# FIT_FPGA_A-B-C.net
KiCad netlist of a schematic drawn in Altium Designer
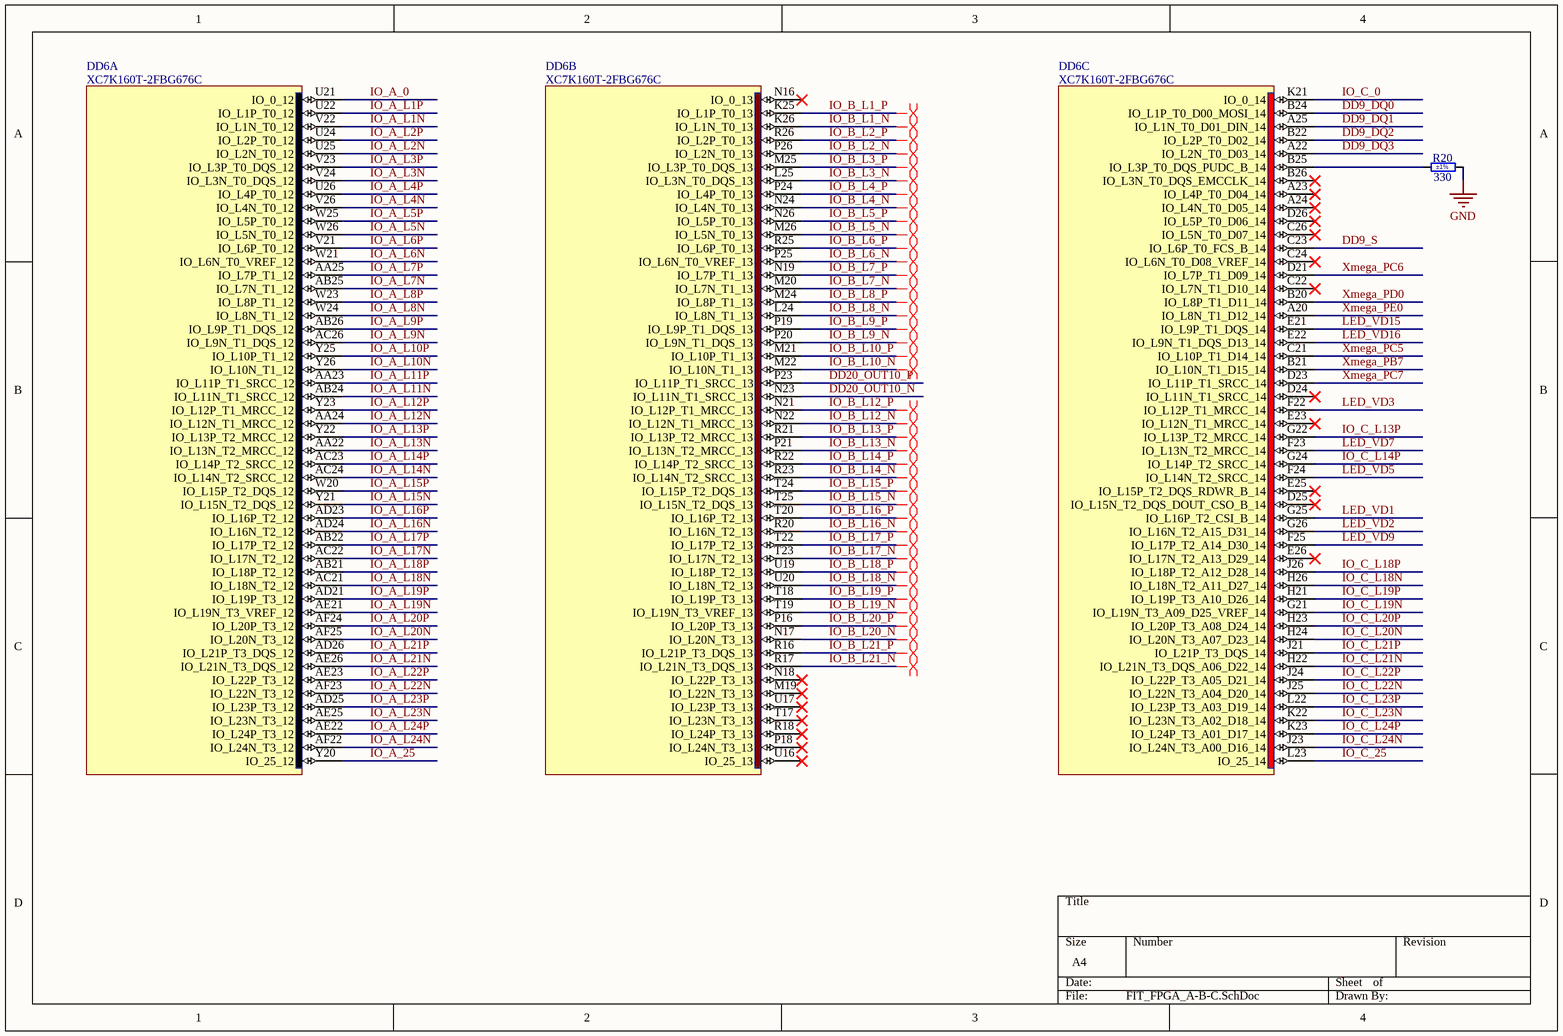
[diagram p0: FIT_FPGA_A-B-C.SchDoc]

(export (version "E")
  (design (tool "Eeschema 10.0.6"))
  (components
    (comp (ref "DD6")
      (value "XC7K160T-2FBG676C")
      (footprint "BGA676C100P26X26_2700X2700X254")
      (description "KINTEX-7, FPGA, 676-Ball BGA, Pb-Free")
      (fields (field (name "MANUFACTURER") "XILINX") (field (name "AUTHOR") "CERN DEM BC"))
      (libsource (lib "ICs And Semiconductors") (part "XC7K160T-xFBG676"))
    )
    (comp (ref "R20")
      (value "330")
      (footprint "RESC2012X60N")
      (description "Resistor - 1%")
      (fields
        (field (name "TOLERANCE") "±1%")
        (field (name "PART NUMBER") "R0805_330R_1%_0.125W_100PPM")
        (field (name "POWER") "0.125W")
        (field (name "AUTHOR") "CERN DEM JLC")
      )
      (libsource (lib "Resistors") (part "Resistor - 1%"))
    )
  )
  (nets
    (net (code "1") (name "/DD9_DQ0") (class "Default")
      (node (ref "DD6") (pin "B24") (pinfunction "IO_L1P_T0_D00_MOSI_14_B24") (pintype "bidirectional"))
    )
    (net (code "2") (name "/DD9_DQ1") (class "Default")
      (node (ref "DD6") (pin "A25") (pinfunction "IO_L1N_T0_D01_DIN_14_A25") (pintype "bidirectional"))
    )
    (net (code "3") (name "/DD9_DQ2") (class "Default")
      (node (ref "DD6") (pin "B22") (pinfunction "IO_L2P_T0_D02_14_B22") (pintype "bidirectional"))
    )
    (net (code "4") (name "/DD9_DQ3") (class "Default")
      (node (ref "DD6") (pin "A22") (pinfunction "IO_L2N_T0_D03_14_A22") (pintype "bidirectional"))
    )
    (net (code "5") (name "/DD9_S") (class "Default")
      (node (ref "DD6") (pin "C23") (pinfunction "IO_L6P_T0_FCS_B_14_C23") (pintype "bidirectional"))
    )
    (net (code "6") (name "/DD20_OUT10_N") (class "Default")
      (node (ref "DD6") (pin "N23") (pinfunction "IO_L11N_T1_SRCC_13_N23") (pintype "bidirectional"))
    )
    (net (code "7") (name "/DD20_OUT10_P") (class "Default")
      (node (ref "DD6") (pin "P23") (pinfunction "IO_L11P_T1_SRCC_13_P23") (pintype "bidirectional"))
    )
    (net (code "8") (name "/IO_A_0") (class "Default")
      (node (ref "DD6") (pin "U21") (pinfunction "IO_0_12_U21") (pintype "bidirectional"))
    )
    (net (code "9") (name "/IO_A_25") (class "Default")
      (node (ref "DD6") (pin "Y20") (pinfunction "IO_25_12_Y20") (pintype "bidirectional"))
    )
    (net (code "10") (name "/IO_A_L1N") (class "Default")
      (node (ref "DD6") (pin "V22") (pinfunction "IO_L1N_T0_12_V22") (pintype "bidirectional"))
    )
    (net (code "11") (name "/IO_A_L1P") (class "Default")
      (node (ref "DD6") (pin "U22") (pinfunction "IO_L1P_T0_12_U22") (pintype "bidirectional"))
    )
    (net (code "12") (name "/IO_A_L2N") (class "Default")
      (node (ref "DD6") (pin "U25") (pinfunction "IO_L2N_T0_12_U25") (pintype "bidirectional"))
    )
    (net (code "13") (name "/IO_A_L2P") (class "Default")
      (node (ref "DD6") (pin "U24") (pinfunction "IO_L2P_T0_12_U24") (pintype "bidirectional"))
    )
    (net (code "14") (name "/IO_A_L3N") (class "Default")
      (node (ref "DD6") (pin "V24") (pinfunction "IO_L3N_T0_DQS_12_V24") (pintype "bidirectional"))
    )
    (net (code "15") (name "/IO_A_L3P") (class "Default")
      (node (ref "DD6") (pin "V23") (pinfunction "IO_L3P_T0_DQS_12_V23") (pintype "bidirectional"))
    )
    (net (code "16") (name "/IO_A_L4N") (class "Default")
      (node (ref "DD6") (pin "V26") (pinfunction "IO_L4N_T0_12_V26") (pintype "bidirectional"))
    )
    (net (code "17") (name "/IO_A_L4P") (class "Default")
      (node (ref "DD6") (pin "U26") (pinfunction "IO_L4P_T0_12_U26") (pintype "bidirectional"))
    )
    (net (code "18") (name "/IO_A_L5N") (class "Default")
      (node (ref "DD6") (pin "W26") (pinfunction "IO_L5N_T0_12_W26") (pintype "bidirectional"))
    )
    (net (code "19") (name "/IO_A_L5P") (class "Default")
      (node (ref "DD6") (pin "W25") (pinfunction "IO_L5P_T0_12_W25") (pintype "bidirectional"))
    )
    (net (code "20") (name "/IO_A_L6N") (class "Default")
      (node (ref "DD6") (pin "W21") (pinfunction "IO_L6N_T0_VREF_12_W21") (pintype "bidirectional"))
    )
    (net (code "21") (name "/IO_A_L6P") (class "Default")
      (node (ref "DD6") (pin "V21") (pinfunction "IO_L6P_T0_12_V21") (pintype "bidirectional"))
    )
    (net (code "22") (name "/IO_A_L7N") (class "Default")
      (node (ref "DD6") (pin "AB25") (pinfunction "IO_L7N_T1_12_AB25") (pintype "bidirectional"))
    )
    (net (code "23") (name "/IO_A_L7P") (class "Default")
      (node (ref "DD6") (pin "AA25") (pinfunction "IO_L7P_T1_12_AA25") (pintype "bidirectional"))
    )
    (net (code "24") (name "/IO_A_L8N") (class "Default")
      (node (ref "DD6") (pin "W24") (pinfunction "IO_L8N_T1_12_W24") (pintype "bidirectional"))
    )
    (net (code "25") (name "/IO_A_L8P") (class "Default")
      (node (ref "DD6") (pin "W23") (pinfunction "IO_L8P_T1_12_W23") (pintype "bidirectional"))
    )
    (net (code "26") (name "/IO_A_L9N") (class "Default")
      (node (ref "DD6") (pin "AC26") (pinfunction "IO_L9N_T1_DQS_12_AC26") (pintype "bidirectional"))
    )
    (net (code "27") (name "/IO_A_L9P") (class "Default")
      (node (ref "DD6") (pin "AB26") (pinfunction "IO_L9P_T1_DQS_12_AB26") (pintype "bidirectional"))
    )
    (net (code "28") (name "/IO_A_L10N") (class "Default")
      (node (ref "DD6") (pin "Y26") (pinfunction "IO_L10N_T1_12_Y26") (pintype "bidirectional"))
    )
    (net (code "29") (name "/IO_A_L10P") (class "Default")
      (node (ref "DD6") (pin "Y25") (pinfunction "IO_L10P_T1_12_Y25") (pintype "bidirectional"))
    )
    (net (code "30") (name "/IO_A_L11N") (class "Default")
      (node (ref "DD6") (pin "AB24") (pinfunction "IO_L11N_T1_SRCC_12_AB24") (pintype "bidirectional"))
    )
    (net (code "31") (name "/IO_A_L11P") (class "Default")
      (node (ref "DD6") (pin "AA23") (pinfunction "IO_L11P_T1_SRCC_12_AA23") (pintype "bidirectional"))
    )
    (net (code "32") (name "/IO_A_L12N") (class "Default")
      (node (ref "DD6") (pin "AA24") (pinfunction "IO_L12N_T1_MRCC_12_AA24") (pintype "bidirectional"))
    )
    (net (code "33") (name "/IO_A_L12P") (class "Default")
      (node (ref "DD6") (pin "Y23") (pinfunction "IO_L12P_T1_MRCC_12_Y23") (pintype "bidirectional"))
    )
    (net (code "34") (name "/IO_A_L13N") (class "Default")
      (node (ref "DD6") (pin "AA22") (pinfunction "IO_L13N_T2_MRCC_12_AA22") (pintype "bidirectional"))
    )
    (net (code "35") (name "/IO_A_L13P") (class "Default")
      (node (ref "DD6") (pin "Y22") (pinfunction "IO_L13P_T2_MRCC_12_Y22") (pintype "bidirectional"))
    )
    (net (code "36") (name "/IO_A_L14N") (class "Default")
      (node (ref "DD6") (pin "AC24") (pinfunction "IO_L14N_T2_SRCC_12_AC24") (pintype "bidirectional"))
    )
    (net (code "37") (name "/IO_A_L14P") (class "Default")
      (node (ref "DD6") (pin "AC23") (pinfunction "IO_L14P_T2_SRCC_12_AC23") (pintype "bidirectional"))
    )
    (net (code "38") (name "/IO_A_L15N") (class "Default")
      (node (ref "DD6") (pin "Y21") (pinfunction "IO_L15N_T2_DQS_12_Y21") (pintype "bidirectional"))
    )
    (net (code "39") (name "/IO_A_L15P") (class "Default")
      (node (ref "DD6") (pin "W20") (pinfunction "IO_L15P_T2_DQS_12_W20") (pintype "bidirectional"))
    )
    (net (code "40") (name "/IO_A_L16N") (class "Default")
      (node (ref "DD6") (pin "AD24") (pinfunction "IO_L16N_T2_12_AD24") (pintype "bidirectional"))
    )
    (net (code "41") (name "/IO_A_L16P") (class "Default")
      (node (ref "DD6") (pin "AD23") (pinfunction "IO_L16P_T2_12_AD23") (pintype "bidirectional"))
    )
    (net (code "42") (name "/IO_A_L17N") (class "Default")
      (node (ref "DD6") (pin "AC22") (pinfunction "IO_L17N_T2_12_AC22") (pintype "bidirectional"))
    )
    (net (code "43") (name "/IO_A_L17P") (class "Default")
      (node (ref "DD6") (pin "AB22") (pinfunction "IO_L17P_T2_12_AB22") (pintype "bidirectional"))
    )
    (net (code "44") (name "/IO_A_L18N") (class "Default")
      (node (ref "DD6") (pin "AC21") (pinfunction "IO_L18N_T2_12_AC21") (pintype "bidirectional"))
    )
    (net (code "45") (name "/IO_A_L18P") (class "Default")
      (node (ref "DD6") (pin "AB21") (pinfunction "IO_L18P_T2_12_AB21") (pintype "bidirectional"))
    )
    (net (code "46") (name "/IO_A_L19N") (class "Default")
      (node (ref "DD6") (pin "AE21") (pinfunction "IO_L19N_T3_VREF_12_AE21") (pintype "bidirectional"))
    )
    (net (code "47") (name "/IO_A_L19P") (class "Default")
      (node (ref "DD6") (pin "AD21") (pinfunction "IO_L19P_T3_12_AD21") (pintype "bidirectional"))
    )
    (net (code "48") (name "/IO_A_L20N") (class "Default")
      (node (ref "DD6") (pin "AF25") (pinfunction "IO_L20N_T3_12_AF25") (pintype "bidirectional"))
    )
    (net (code "49") (name "/IO_A_L20P") (class "Default")
      (node (ref "DD6") (pin "AF24") (pinfunction "IO_L20P_T3_12_AF24") (pintype "bidirectional"))
    )
    (net (code "50") (name "/IO_A_L21N") (class "Default")
      (node (ref "DD6") (pin "AE26") (pinfunction "IO_L21N_T3_DQS_12_AE26") (pintype "bidirectional"))
    )
    (net (code "51") (name "/IO_A_L21P") (class "Default")
      (node (ref "DD6") (pin "AD26") (pinfunction "IO_L21P_T3_DQS_12_AD26") (pintype "bidirectional"))
    )
    (net (code "52") (name "/IO_A_L22N") (class "Default")
      (node (ref "DD6") (pin "AF23") (pinfunction "IO_L22N_T3_12_AF23") (pintype "bidirectional"))
    )
    (net (code "53") (name "/IO_A_L22P") (class "Default")
      (node (ref "DD6") (pin "AE23") (pinfunction "IO_L22P_T3_12_AE23") (pintype "bidirectional"))
    )
    (net (code "54") (name "/IO_A_L23N") (class "Default")
      (node (ref "DD6") (pin "AE25") (pinfunction "IO_L23N_T3_12_AE25") (pintype "bidirectional"))
    )
    (net (code "55") (name "/IO_A_L23P") (class "Default")
      (node (ref "DD6") (pin "AD25") (pinfunction "IO_L23P_T3_12_AD25") (pintype "bidirectional"))
    )
    (net (code "56") (name "/IO_A_L24N") (class "Default")
      (node (ref "DD6") (pin "AF22") (pinfunction "IO_L24N_T3_12_AF22") (pintype "bidirectional"))
    )
    (net (code "57") (name "/IO_A_L24P") (class "Default")
      (node (ref "DD6") (pin "AE22") (pinfunction "IO_L24P_T3_12_AE22") (pintype "bidirectional"))
    )
    (net (code "58") (name "/IO_B_L1_N") (class "Default")
      (node (ref "DD6") (pin "K26") (pinfunction "IO_L1N_T0_13_K26") (pintype "bidirectional"))
    )
    (net (code "59") (name "/IO_B_L1_P") (class "Default")
      (node (ref "DD6") (pin "K25") (pinfunction "IO_L1P_T0_13_K25") (pintype "bidirectional"))
    )
    (net (code "60") (name "/IO_B_L2_N") (class "Default")
      (node (ref "DD6") (pin "P26") (pinfunction "IO_L2N_T0_13_P26") (pintype "bidirectional"))
    )
    (net (code "61") (name "/IO_B_L2_P") (class "Default")
      (node (ref "DD6") (pin "R26") (pinfunction "IO_L2P_T0_13_R26") (pintype "bidirectional"))
    )
    (net (code "62") (name "/IO_B_L3_N") (class "Default")
      (node (ref "DD6") (pin "L25") (pinfunction "IO_L3N_T0_DQS_13_L25") (pintype "bidirectional"))
    )
    (net (code "63") (name "/IO_B_L3_P") (class "Default")
      (node (ref "DD6") (pin "M25") (pinfunction "IO_L3P_T0_DQS_13_M25") (pintype "bidirectional"))
    )
    (net (code "64") (name "/IO_B_L4_N") (class "Default")
      (node (ref "DD6") (pin "N24") (pinfunction "IO_L4N_T0_13_N24") (pintype "bidirectional"))
    )
    (net (code "65") (name "/IO_B_L4_P") (class "Default")
      (node (ref "DD6") (pin "P24") (pinfunction "IO_L4P_T0_13_P24") (pintype "bidirectional"))
    )
    (net (code "66") (name "/IO_B_L5_N") (class "Default")
      (node (ref "DD6") (pin "M26") (pinfunction "IO_L5N_T0_13_M26") (pintype "bidirectional"))
    )
    (net (code "67") (name "/IO_B_L5_P") (class "Default")
      (node (ref "DD6") (pin "N26") (pinfunction "IO_L5P_T0_13_N26") (pintype "bidirectional"))
    )
    (net (code "68") (name "/IO_B_L6_N") (class "Default")
      (node (ref "DD6") (pin "P25") (pinfunction "IO_L6N_T0_VREF_13_P25") (pintype "bidirectional"))
    )
    (net (code "69") (name "/IO_B_L6_P") (class "Default")
      (node (ref "DD6") (pin "R25") (pinfunction "IO_L6P_T0_13_R25") (pintype "bidirectional"))
    )
    (net (code "70") (name "/IO_B_L7_N") (class "Default")
      (node (ref "DD6") (pin "M20") (pinfunction "IO_L7N_T1_13_M20") (pintype "bidirectional"))
    )
    (net (code "71") (name "/IO_B_L7_P") (class "Default")
      (node (ref "DD6") (pin "N19") (pinfunction "IO_L7P_T1_13_N19") (pintype "bidirectional"))
    )
    (net (code "72") (name "/IO_B_L8_N") (class "Default")
      (node (ref "DD6") (pin "L24") (pinfunction "IO_L8N_T1_13_L24") (pintype "bidirectional"))
    )
    (net (code "73") (name "/IO_B_L8_P") (class "Default")
      (node (ref "DD6") (pin "M24") (pinfunction "IO_L8P_T1_13_M24") (pintype "bidirectional"))
    )
    (net (code "74") (name "/IO_B_L9_N") (class "Default")
      (node (ref "DD6") (pin "P20") (pinfunction "IO_L9N_T1_DQS_13_P20") (pintype "bidirectional"))
    )
    (net (code "75") (name "/IO_B_L9_P") (class "Default")
      (node (ref "DD6") (pin "P19") (pinfunction "IO_L9P_T1_DQS_13_P19") (pintype "bidirectional"))
    )
    (net (code "76") (name "/IO_B_L10_N") (class "Default")
      (node (ref "DD6") (pin "M22") (pinfunction "IO_L10N_T1_13_M22") (pintype "bidirectional"))
    )
    (net (code "77") (name "/IO_B_L10_P") (class "Default")
      (node (ref "DD6") (pin "M21") (pinfunction "IO_L10P_T1_13_M21") (pintype "bidirectional"))
    )
    (net (code "78") (name "/IO_B_L12_N") (class "Default")
      (node (ref "DD6") (pin "N22") (pinfunction "IO_L12N_T1_MRCC_13_N22") (pintype "bidirectional"))
    )
    (net (code "79") (name "/IO_B_L12_P") (class "Default")
      (node (ref "DD6") (pin "N21") (pinfunction "IO_L12P_T1_MRCC_13_N21") (pintype "bidirectional"))
    )
    (net (code "80") (name "/IO_B_L13_N") (class "Default")
      (node (ref "DD6") (pin "P21") (pinfunction "IO_L13N_T2_MRCC_13_P21") (pintype "bidirectional"))
    )
    (net (code "81") (name "/IO_B_L13_P") (class "Default")
      (node (ref "DD6") (pin "R21") (pinfunction "IO_L13P_T2_MRCC_13_R21") (pintype "bidirectional"))
    )
    (net (code "82") (name "/IO_B_L14_N") (class "Default")
      (node (ref "DD6") (pin "R23") (pinfunction "IO_L14N_T2_SRCC_13_R23") (pintype "bidirectional"))
    )
    (net (code "83") (name "/IO_B_L14_P") (class "Default")
      (node (ref "DD6") (pin "R22") (pinfunction "IO_L14P_T2_SRCC_13_R22") (pintype "bidirectional"))
    )
    (net (code "84") (name "/IO_B_L15_N") (class "Default")
      (node (ref "DD6") (pin "T25") (pinfunction "IO_L15N_T2_DQS_13_T25") (pintype "bidirectional"))
    )
    (net (code "85") (name "/IO_B_L15_P") (class "Default")
      (node (ref "DD6") (pin "T24") (pinfunction "IO_L15P_T2_DQS_13_T24") (pintype "bidirectional"))
    )
    (net (code "86") (name "/IO_B_L16_N") (class "Default")
      (node (ref "DD6") (pin "R20") (pinfunction "IO_L16N_T2_13_R20") (pintype "bidirectional"))
    )
    (net (code "87") (name "/IO_B_L16_P") (class "Default")
      (node (ref "DD6") (pin "T20") (pinfunction "IO_L16P_T2_13_T20") (pintype "bidirectional"))
    )
    (net (code "88") (name "/IO_B_L17_N") (class "Default")
      (node (ref "DD6") (pin "T23") (pinfunction "IO_L17N_T2_13_T23") (pintype "bidirectional"))
    )
    (net (code "89") (name "/IO_B_L17_P") (class "Default")
      (node (ref "DD6") (pin "T22") (pinfunction "IO_L17P_T2_13_T22") (pintype "bidirectional"))
    )
    (net (code "90") (name "/IO_B_L18_N") (class "Default")
      (node (ref "DD6") (pin "U20") (pinfunction "IO_L18N_T2_13_U20") (pintype "bidirectional"))
    )
    (net (code "91") (name "/IO_B_L18_P") (class "Default")
      (node (ref "DD6") (pin "U19") (pinfunction "IO_L18P_T2_13_U19") (pintype "bidirectional"))
    )
    (net (code "92") (name "/IO_B_L19_N") (class "Default")
      (node (ref "DD6") (pin "T19") (pinfunction "IO_L19N_T3_VREF_13_T19") (pintype "bidirectional"))
    )
    (net (code "93") (name "/IO_B_L19_P") (class "Default")
      (node (ref "DD6") (pin "T18") (pinfunction "IO_L19P_T3_13_T18") (pintype "bidirectional"))
    )
    (net (code "94") (name "/IO_B_L20_N") (class "Default")
      (node (ref "DD6") (pin "N17") (pinfunction "IO_L20N_T3_13_N17") (pintype "bidirectional"))
    )
    (net (code "95") (name "/IO_B_L20_P") (class "Default")
      (node (ref "DD6") (pin "P16") (pinfunction "IO_L20P_T3_13_P16") (pintype "bidirectional"))
    )
    (net (code "96") (name "/IO_B_L21_N") (class "Default")
      (node (ref "DD6") (pin "R17") (pinfunction "IO_L21N_T3_DQS_13_R17") (pintype "bidirectional"))
    )
    (net (code "97") (name "/IO_B_L21_P") (class "Default")
      (node (ref "DD6") (pin "R16") (pinfunction "IO_L21P_T3_DQS_13_R16") (pintype "bidirectional"))
    )
    (net (code "98") (name "/IO_C_0") (class "Default")
      (node (ref "DD6") (pin "K21") (pinfunction "IO_0_14_K21") (pintype "bidirectional"))
    )
    (net (code "99") (name "/IO_C_25") (class "Default")
      (node (ref "DD6") (pin "L23") (pinfunction "IO_25_14_L23") (pintype "bidirectional"))
    )
    (net (code "100") (name "/IO_C_L13P") (class "Default")
      (node (ref "DD6") (pin "G22") (pinfunction "IO_L13P_T2_MRCC_14_G22") (pintype "bidirectional"))
    )
    (net (code "101") (name "/IO_C_L14P") (class "Default")
      (node (ref "DD6") (pin "G24") (pinfunction "IO_L14P_T2_SRCC_14_G24") (pintype "bidirectional"))
    )
    (net (code "102") (name "/IO_C_L18N") (class "Default")
      (node (ref "DD6") (pin "H26") (pinfunction "IO_L18N_T2_A11_D27_14_H26") (pintype "bidirectional"))
    )
    (net (code "103") (name "/IO_C_L18P") (class "Default")
      (node (ref "DD6") (pin "J26") (pinfunction "IO_L18P_T2_A12_D28_14_J26") (pintype "bidirectional"))
    )
    (net (code "104") (name "/IO_C_L19N") (class "Default")
      (node (ref "DD6") (pin "G21") (pinfunction "IO_L19N_T3_A09_D25_VREF_14_G21") (pintype "bidirectional"))
    )
    (net (code "105") (name "/IO_C_L19P") (class "Default")
      (node (ref "DD6") (pin "H21") (pinfunction "IO_L19P_T3_A10_D26_14_H21") (pintype "bidirectional"))
    )
    (net (code "106") (name "/IO_C_L20N") (class "Default")
      (node (ref "DD6") (pin "H24") (pinfunction "IO_L20N_T3_A07_D23_14_H24") (pintype "bidirectional"))
    )
    (net (code "107") (name "/IO_C_L20P") (class "Default")
      (node (ref "DD6") (pin "H23") (pinfunction "IO_L20P_T3_A08_D24_14_H23") (pintype "bidirectional"))
    )
    (net (code "108") (name "/IO_C_L21N") (class "Default")
      (node (ref "DD6") (pin "H22") (pinfunction "IO_L21N_T3_DQS_A06_D22_14_H22") (pintype "bidirectional"))
    )
    (net (code "109") (name "/IO_C_L21P") (class "Default")
      (node (ref "DD6") (pin "J21") (pinfunction "IO_L21P_T3_DQS_14_J21") (pintype "bidirectional"))
    )
    (net (code "110") (name "/IO_C_L22N") (class "Default")
      (node (ref "DD6") (pin "J25") (pinfunction "IO_L22N_T3_A04_D20_14_J25") (pintype "bidirectional"))
    )
    (net (code "111") (name "/IO_C_L22P") (class "Default")
      (node (ref "DD6") (pin "J24") (pinfunction "IO_L22P_T3_A05_D21_14_J24") (pintype "bidirectional"))
    )
    (net (code "112") (name "/IO_C_L23N") (class "Default")
      (node (ref "DD6") (pin "K22") (pinfunction "IO_L23N_T3_A02_D18_14_K22") (pintype "bidirectional"))
    )
    (net (code "113") (name "/IO_C_L23P") (class "Default")
      (node (ref "DD6") (pin "L22") (pinfunction "IO_L23P_T3_A03_D19_14_L22") (pintype "bidirectional"))
    )
    (net (code "114") (name "/IO_C_L24N") (class "Default")
      (node (ref "DD6") (pin "J23") (pinfunction "IO_L24N_T3_A00_D16_14_J23") (pintype "bidirectional"))
    )
    (net (code "115") (name "/IO_C_L24P") (class "Default")
      (node (ref "DD6") (pin "K23") (pinfunction "IO_L24P_T3_A01_D17_14_K23") (pintype "bidirectional"))
    )
    (net (code "116") (name "/LED_VD1") (class "Default")
      (node (ref "DD6") (pin "G25") (pinfunction "IO_L16P_T2_CSI_B_14_G25") (pintype "bidirectional"))
    )
    (net (code "117") (name "/LED_VD2") (class "Default")
      (node (ref "DD6") (pin "G26") (pinfunction "IO_L16N_T2_A15_D31_14_G26") (pintype "bidirectional"))
    )
    (net (code "118") (name "/LED_VD3") (class "Default")
      (node (ref "DD6") (pin "F22") (pinfunction "IO_L12P_T1_MRCC_14_F22") (pintype "bidirectional"))
    )
    (net (code "119") (name "/LED_VD5") (class "Default")
      (node (ref "DD6") (pin "F24") (pinfunction "IO_L14N_T2_SRCC_14_F24") (pintype "bidirectional"))
    )
    (net (code "120") (name "/LED_VD7") (class "Default")
      (node (ref "DD6") (pin "F23") (pinfunction "IO_L13N_T2_MRCC_14_F23") (pintype "bidirectional"))
    )
    (net (code "121") (name "/LED_VD9") (class "Default")
      (node (ref "DD6") (pin "F25") (pinfunction "IO_L17P_T2_A14_D30_14_F25") (pintype "bidirectional"))
    )
    (net (code "122") (name "/LED_VD15") (class "Default")
      (node (ref "DD6") (pin "E21") (pinfunction "IO_L9P_T1_DQS_14_E21") (pintype "bidirectional"))
    )
    (net (code "123") (name "/LED_VD16") (class "Default")
      (node (ref "DD6") (pin "E22") (pinfunction "IO_L9N_T1_DQS_D13_14_E22") (pintype "bidirectional"))
    )
    (net (code "124") (name "/Xmega_PB7") (class "Default")
      (node (ref "DD6") (pin "B21") (pinfunction "IO_L10N_T1_D15_14_B21") (pintype "bidirectional"))
    )
    (net (code "125") (name "/Xmega_PC5") (class "Default")
      (node (ref "DD6") (pin "C21") (pinfunction "IO_L10P_T1_D14_14_C21") (pintype "bidirectional"))
    )
    (net (code "126") (name "/Xmega_PC6") (class "Default")
      (node (ref "DD6") (pin "D21") (pinfunction "IO_L7P_T1_D09_14_D21") (pintype "bidirectional"))
    )
    (net (code "127") (name "/Xmega_PC7") (class "Default")
      (node (ref "DD6") (pin "D23") (pinfunction "IO_L11P_T1_SRCC_14_D23") (pintype "bidirectional"))
    )
    (net (code "128") (name "/Xmega_PD0") (class "Default")
      (node (ref "DD6") (pin "B20") (pinfunction "IO_L8P_T1_D11_14_B20") (pintype "bidirectional"))
    )
    (net (code "129") (name "/Xmega_PE0") (class "Default")
      (node (ref "DD6") (pin "A20") (pinfunction "IO_L8N_T1_D12_14_A20") (pintype "bidirectional"))
    )
    (net (code "130") (name "GND") (class "Default")
      (node (ref "R20") (pin "2") (pinfunction "2_2") (pintype "passive"))
    )
    (net (code "131") (name "Net-(DD6C-IO_L3P_T0_DQS_PUDC_B_14)") (class "Default")
      (node (ref "DD6") (pin "B25") (pinfunction "IO_L3P_T0_DQS_PUDC_B_14_B25") (pintype "bidirectional"))
      (node (ref "R20") (pin "1") (pinfunction "1_1") (pintype "passive"))
    )
    (net (code "132") (name "unconnected-(DD6B-IO_0_13-PadN16)") (class "Default")
      (node (ref "DD6") (pin "N16") (pinfunction "IO_0_13_N16") (pintype "bidirectional+no_connect"))
    )
    (net (code "133") (name "unconnected-(DD6B-IO_25_13-PadU16)") (class "Default")
      (node (ref "DD6") (pin "U16") (pinfunction "IO_25_13_U16") (pintype "bidirectional+no_connect"))
    )
    (net (code "134") (name "unconnected-(DD6B-IO_L22N_T3_13-PadM19)") (class "Default")
      (node (ref "DD6") (pin "M19") (pinfunction "IO_L22N_T3_13_M19") (pintype "bidirectional+no_connect"))
    )
    (net (code "135") (name "unconnected-(DD6B-IO_L22P_T3_13-PadN18)") (class "Default")
      (node (ref "DD6") (pin "N18") (pinfunction "IO_L22P_T3_13_N18") (pintype "bidirectional+no_connect"))
    )
    (net (code "136") (name "unconnected-(DD6B-IO_L23N_T3_13-PadT17)") (class "Default")
      (node (ref "DD6") (pin "T17") (pinfunction "IO_L23N_T3_13_T17") (pintype "bidirectional+no_connect"))
    )
    (net (code "137") (name "unconnected-(DD6B-IO_L23P_T3_13-PadU17)") (class "Default")
      (node (ref "DD6") (pin "U17") (pinfunction "IO_L23P_T3_13_U17") (pintype "bidirectional+no_connect"))
    )
    (net (code "138") (name "unconnected-(DD6B-IO_L24N_T3_13-PadP18)") (class "Default")
      (node (ref "DD6") (pin "P18") (pinfunction "IO_L24N_T3_13_P18") (pintype "bidirectional+no_connect"))
    )
    (net (code "139") (name "unconnected-(DD6B-IO_L24P_T3_13-PadR18)") (class "Default")
      (node (ref "DD6") (pin "R18") (pinfunction "IO_L24P_T3_13_R18") (pintype "bidirectional+no_connect"))
    )
    (net (code "140") (name "unconnected-(DD6C-IO_L3N_T0_DQS_EMCCLK_14-PadB26)") (class "Default")
      (node (ref "DD6") (pin "B26") (pinfunction "IO_L3N_T0_DQS_EMCCLK_14_B26") (pintype "bidirectional+no_connect"))
    )
    (net (code "141") (name "unconnected-(DD6C-IO_L4N_T0_D05_14-PadA24)") (class "Default")
      (node (ref "DD6") (pin "A24") (pinfunction "IO_L4N_T0_D05_14_A24") (pintype "bidirectional+no_connect"))
    )
    (net (code "142") (name "unconnected-(DD6C-IO_L4P_T0_D04_14-PadA23)") (class "Default")
      (node (ref "DD6") (pin "A23") (pinfunction "IO_L4P_T0_D04_14_A23") (pintype "bidirectional+no_connect"))
    )
    (net (code "143") (name "unconnected-(DD6C-IO_L5N_T0_D07_14-PadC26)") (class "Default")
      (node (ref "DD6") (pin "C26") (pinfunction "IO_L5N_T0_D07_14_C26") (pintype "bidirectional+no_connect"))
    )
    (net (code "144") (name "unconnected-(DD6C-IO_L5P_T0_D06_14-PadD26)") (class "Default")
      (node (ref "DD6") (pin "D26") (pinfunction "IO_L5P_T0_D06_14_D26") (pintype "bidirectional+no_connect"))
    )
    (net (code "145") (name "unconnected-(DD6C-IO_L6N_T0_D08_VREF_14-PadC24)") (class "Default")
      (node (ref "DD6") (pin "C24") (pinfunction "IO_L6N_T0_D08_VREF_14_C24") (pintype "bidirectional+no_connect"))
    )
    (net (code "146") (name "unconnected-(DD6C-IO_L7N_T1_D10_14-PadC22)") (class "Default")
      (node (ref "DD6") (pin "C22") (pinfunction "IO_L7N_T1_D10_14_C22") (pintype "bidirectional+no_connect"))
    )
    (net (code "147") (name "unconnected-(DD6C-IO_L11N_T1_SRCC_14-PadD24)") (class "Default")
      (node (ref "DD6") (pin "D24") (pinfunction "IO_L11N_T1_SRCC_14_D24") (pintype "bidirectional+no_connect"))
    )
    (net (code "148") (name "unconnected-(DD6C-IO_L12N_T1_MRCC_14-PadE23)") (class "Default")
      (node (ref "DD6") (pin "E23") (pinfunction "IO_L12N_T1_MRCC_14_E23") (pintype "bidirectional+no_connect"))
    )
    (net (code "149") (name "unconnected-(DD6C-IO_L15N_T2_DQS_DOUT_CSO_B_14-PadD25)") (class "Default")
      (node (ref "DD6") (pin "D25") (pinfunction "IO_L15N_T2_DQS_DOUT_CSO_B_14_D25") (pintype "bidirectional+no_connect"))
    )
    (net (code "150") (name "unconnected-(DD6C-IO_L15P_T2_DQS_RDWR_B_14-PadE25)") (class "Default")
      (node (ref "DD6") (pin "E25") (pinfunction "IO_L15P_T2_DQS_RDWR_B_14_E25") (pintype "bidirectional+no_connect"))
    )
    (net (code "151") (name "unconnected-(DD6C-IO_L17N_T2_A13_D29_14-PadE26)") (class "Default")
      (node (ref "DD6") (pin "E26") (pinfunction "IO_L17N_T2_A13_D29_14_E26") (pintype "bidirectional+no_connect"))
    )
  )
)
